# GroundPins.net
KiCad netlist of a schematic drawn in Altium Designer
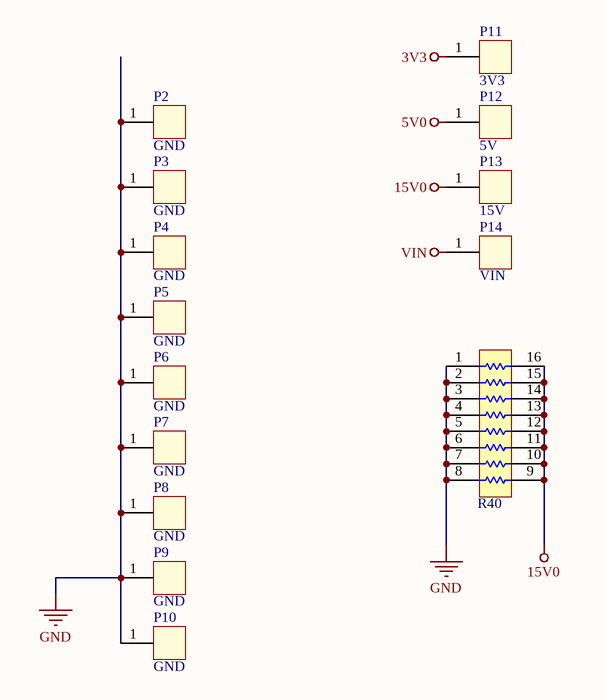
[diagram p0: GroundPins.SchDoc]

(export (version "E")
  (design (tool "Eeschema 10.0.6"))
  (components
    (comp (ref "P2")
      (value "GND")
      (footprint "PinHeader1")
      (description "Pin Header with 1 terminal")
      (fields (field (name "CREATED") "2020-01-08_Thilo_Wendt"))
      (libsource (lib "connectors") (part "PinHeader1"))
    )
    (comp (ref "P3")
      (value "GND")
      (footprint "PinHeader1")
      (description "Pin Header with 1 terminal")
      (fields (field (name "CREATED") "2020-01-08_Thilo_Wendt"))
      (libsource (lib "connectors") (part "PinHeader1"))
    )
    (comp (ref "P4")
      (value "GND")
      (footprint "PinHeader1")
      (description "Pin Header with 1 terminal")
      (fields (field (name "CREATED") "2020-01-08_Thilo_Wendt"))
      (libsource (lib "connectors") (part "PinHeader1"))
    )
    (comp (ref "P5")
      (value "GND")
      (footprint "PinHeader1")
      (description "Pin Header with 1 terminal")
      (fields (field (name "CREATED") "2020-01-08_Thilo_Wendt"))
      (libsource (lib "connectors") (part "PinHeader1"))
    )
    (comp (ref "P6")
      (value "GND")
      (footprint "PinHeader1")
      (description "Pin Header with 1 terminal")
      (fields (field (name "CREATED") "2020-01-08_Thilo_Wendt"))
      (libsource (lib "connectors") (part "PinHeader1"))
    )
    (comp (ref "P7")
      (value "GND")
      (footprint "PinHeader1")
      (description "Pin Header with 1 terminal")
      (fields (field (name "CREATED") "2020-01-08_Thilo_Wendt"))
      (libsource (lib "connectors") (part "PinHeader1"))
    )
    (comp (ref "P8")
      (value "GND")
      (footprint "PinHeader1")
      (description "Pin Header with 1 terminal")
      (fields (field (name "CREATED") "2020-01-08_Thilo_Wendt"))
      (libsource (lib "connectors") (part "PinHeader1"))
    )
    (comp (ref "P9")
      (value "GND")
      (footprint "PinHeader1")
      (description "Pin Header with 1 terminal")
      (fields (field (name "CREATED") "2020-01-08_Thilo_Wendt"))
      (libsource (lib "connectors") (part "PinHeader1"))
    )
    (comp (ref "P10")
      (value "GND")
      (footprint "PinHeader1")
      (description "Pin Header with 1 terminal")
      (fields (field (name "CREATED") "2020-01-08_Thilo_Wendt"))
      (libsource (lib "connectors") (part "PinHeader1"))
    )
    (comp (ref "P11")
      (value "3V3")
      (footprint "PinHeader1")
      (description "Pin Header with 1 terminal")
      (fields (field (name "CREATED") "2020-01-08_Thilo_Wendt"))
      (libsource (lib "connectors") (part "PinHeader1"))
    )
    (comp (ref "P12")
      (value "5V")
      (footprint "PinHeader1")
      (description "Pin Header with 1 terminal")
      (fields (field (name "CREATED") "2020-01-08_Thilo_Wendt"))
      (libsource (lib "connectors") (part "PinHeader1"))
    )
    (comp (ref "P13")
      (value "15V")
      (footprint "PinHeader1")
      (description "Pin Header with 1 terminal")
      (fields (field (name "CREATED") "2020-01-08_Thilo_Wendt"))
      (libsource (lib "connectors") (part "PinHeader1"))
    )
    (comp (ref "P14")
      (value "VIN")
      (footprint "PinHeader1")
      (description "Pin Header with 1 terminal")
      (fields (field (name "CREATED") "2020-01-08_Thilo_Wendt"))
      (libsource (lib "connectors") (part "PinHeader1"))
    )
    (comp (ref "R40")
      (value "0.063W")
      (footprint "RESCAXE-50P380X160X45-16N")
      (description "Standard thick film resistor array with 8 resistors")
      (fields (field (name "CREATED") "2020-01-03_Thilo_Wendt"))
      (libsource (lib "standard_rlc") (part "8xR-Array_1_part"))
    )
  )
  (nets
    (net (code "1") (name "3V3") (class "Default")
      (node (ref "P11") (pin "1") (pinfunction "1_1") (pintype "passive"))
    )
    (net (code "2") (name "5V0") (class "Default")
      (node (ref "P12") (pin "1") (pinfunction "1_1") (pintype "passive"))
    )
    (net (code "3") (name "15V0") (class "Default")
      (node (ref "P13") (pin "1") (pinfunction "1_1") (pintype "passive"))
      (node (ref "R40") (pin "10") (pinfunction "10_10") (pintype "passive"))
      (node (ref "R40") (pin "11") (pinfunction "11_11") (pintype "passive"))
      (node (ref "R40") (pin "12") (pinfunction "12_12") (pintype "passive"))
      (node (ref "R40") (pin "13") (pinfunction "13_13") (pintype "passive"))
      (node (ref "R40") (pin "14") (pinfunction "14_14") (pintype "passive"))
      (node (ref "R40") (pin "15") (pinfunction "15_15") (pintype "passive"))
      (node (ref "R40") (pin "16") (pinfunction "16_16") (pintype "passive"))
      (node (ref "R40") (pin "9") (pinfunction "9_9") (pintype "passive"))
    )
    (net (code "4") (name "GND") (class "Default")
      (node (ref "P10") (pin "1") (pinfunction "1_1") (pintype "passive"))
      (node (ref "P2") (pin "1") (pinfunction "1_1") (pintype "passive"))
      (node (ref "P3") (pin "1") (pinfunction "1_1") (pintype "passive"))
      (node (ref "P4") (pin "1") (pinfunction "1_1") (pintype "passive"))
      (node (ref "P5") (pin "1") (pinfunction "1_1") (pintype "passive"))
      (node (ref "P6") (pin "1") (pinfunction "1_1") (pintype "passive"))
      (node (ref "P7") (pin "1") (pinfunction "1_1") (pintype "passive"))
      (node (ref "P8") (pin "1") (pinfunction "1_1") (pintype "passive"))
      (node (ref "P9") (pin "1") (pinfunction "1_1") (pintype "passive"))
      (node (ref "R40") (pin "1") (pinfunction "1_1") (pintype "passive"))
      (node (ref "R40") (pin "2") (pinfunction "2_2") (pintype "passive"))
      (node (ref "R40") (pin "3") (pinfunction "3_3") (pintype "passive"))
      (node (ref "R40") (pin "4") (pinfunction "4_4") (pintype "passive"))
      (node (ref "R40") (pin "5") (pinfunction "5_5") (pintype "passive"))
      (node (ref "R40") (pin "6") (pinfunction "6_6") (pintype "passive"))
      (node (ref "R40") (pin "7") (pinfunction "7_7") (pintype "passive"))
      (node (ref "R40") (pin "8") (pinfunction "8_8") (pintype "passive"))
    )
    (net (code "5") (name "VIN") (class "Default")
      (node (ref "P14") (pin "1") (pinfunction "1_1") (pintype "passive"))
    )
  )
)
